# G11-KeyDispPrint.net
KiCad netlist of a schematic drawn in Altium Designer
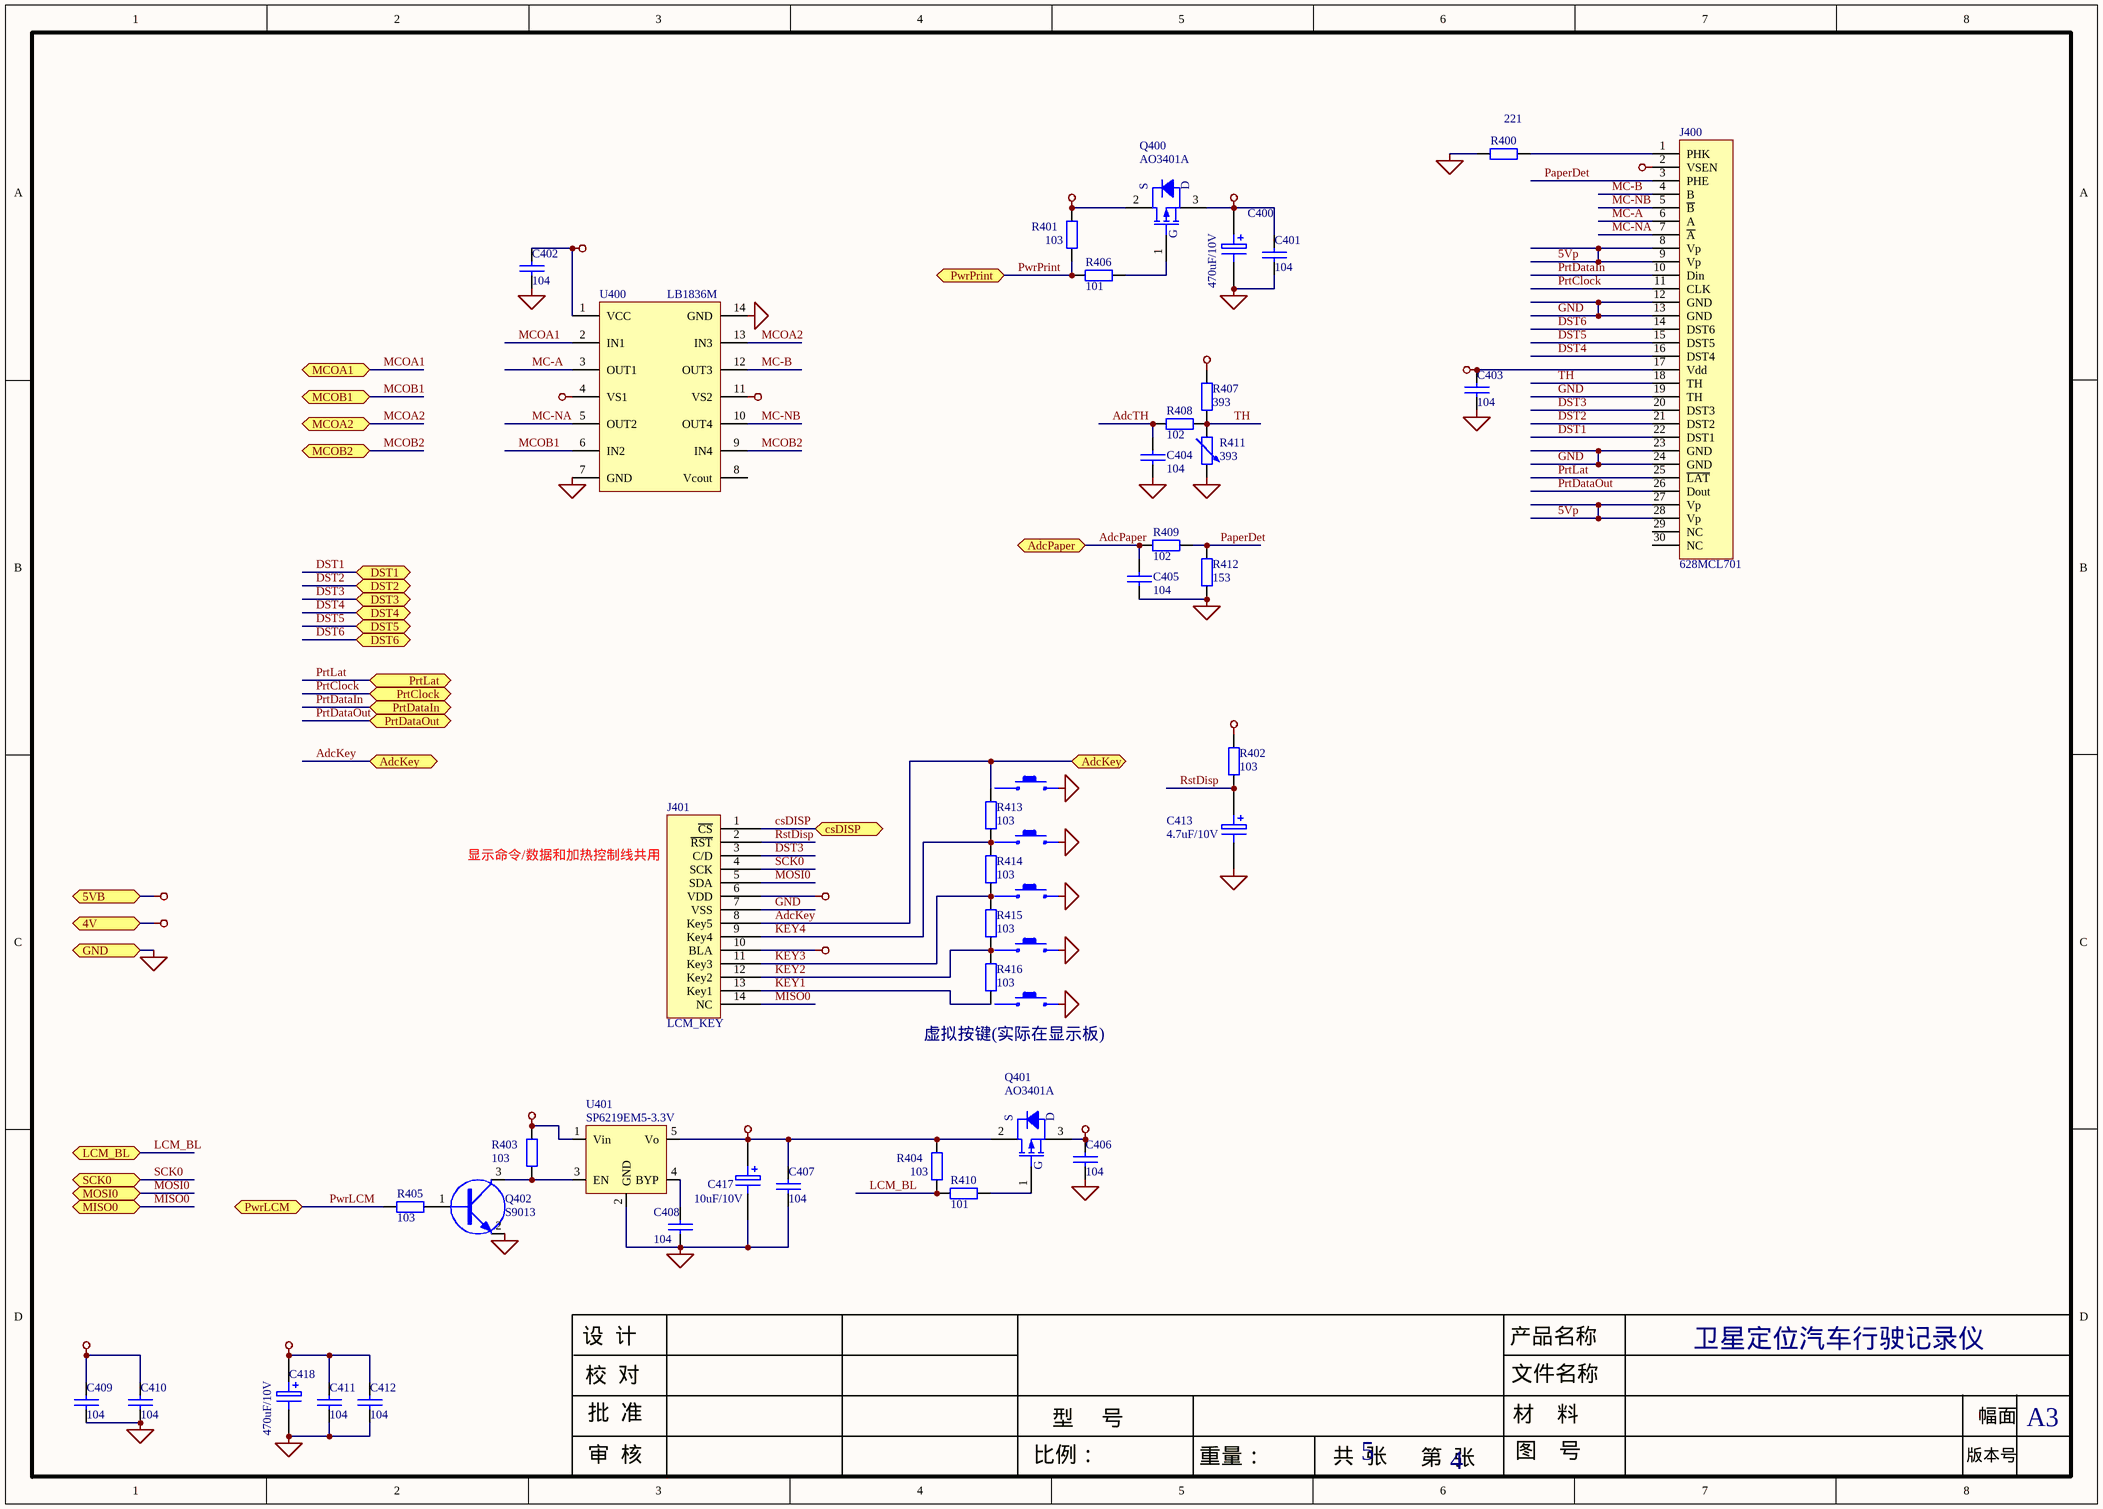
[diagram p0: G11-KeyDispPrint.SCHDOC]

(export (version "E")
  (design (tool "Eeschema 10.0.6"))
  (components
    (comp (ref "C400")
      (value "470uF/10V")
      (footprint "RB-3.5mm")
      (description "直插电解")
      (libsource (lib "*") (part "ELECTRO1"))
    )
    (comp (ref "C401")
      (value "104")
      (footprint "C0603")
      (description "Capacitor")
      (libsource (lib "*") (part "CAP"))
    )
    (comp (ref "C402")
      (value "104")
      (footprint "C0603")
      (description "Capacitor")
      (libsource (lib "*") (part "CAP"))
    )
    (comp (ref "C403")
      (value "104")
      (footprint "C0603")
      (description "Capacitor")
      (libsource (lib "*") (part "CAP"))
    )
    (comp (ref "C404")
      (value "104")
      (footprint "C0603")
      (description "Capacitor")
      (libsource (lib "*") (part "CAP"))
    )
    (comp (ref "C405")
      (value "104")
      (footprint "C0603")
      (description "Capacitor")
      (libsource (lib "*") (part "CAP"))
    )
    (comp (ref "C406")
      (value "104")
      (footprint "C0603")
      (description "Capacitor")
      (libsource (lib "*") (part "CAP"))
    )
    (comp (ref "C407")
      (value "104")
      (footprint "C0603")
      (description "Capacitor")
      (libsource (lib "*") (part "CAP"))
    )
    (comp (ref "C408")
      (value "104")
      (footprint "C0603")
      (description "Capacitor")
      (libsource (lib "*") (part "CAP"))
    )
    (comp (ref "C409")
      (value "104")
      (footprint "C0603")
      (description "Capacitor")
      (libsource (lib "*") (part "CAP"))
    )
    (comp (ref "C410")
      (value "104")
      (footprint "C0603")
      (description "Capacitor")
      (libsource (lib "*") (part "CAP"))
    )
    (comp (ref "C411")
      (value "104")
      (footprint "C0603")
      (description "Capacitor")
      (libsource (lib "*") (part "CAP"))
    )
    (comp (ref "C412")
      (value "104")
      (footprint "C0603")
      (description "Capacitor")
      (libsource (lib "*") (part "CAP"))
    )
    (comp (ref "C413")
      (value "4.7uF/10V")
      (footprint "A(3216)")
      (description "贴片钽电容")
      (libsource (lib "*") (part "ELECTRO1"))
    )
    (comp (ref "C417")
      (value "10uF/10V")
      (footprint "A(3216)")
      (description "贴片钽电容")
      (libsource (lib "*") (part "ELECTRO1"))
    )
    (comp (ref "C418")
      (value "470uF/10V")
      (footprint "RB-3.5mm")
      (description "直插电解")
      (libsource (lib "*") (part "ELECTRO1"))
    )
    (comp (ref "J400")
      (value "628MCL701")
      (footprint "FPC-30H")
      (description "贴片竖焊打印机接口")
      (libsource (lib "GY-G10A_1") (part "628MCL701"))
    )
    (comp (ref "J401") (value "LCM_KEY") (footprint "FPC-14-1.0") (libsource (lib "GY-G11") (part "LCM_KEY")))
    (comp (ref "Q400")
      (value "AO3401A")
      (footprint "SOT-233PM")
      (description "贴片P沟MOS管")
      (libsource (lib "GY-G11") (part "MOSFET-P"))
    )
    (comp (ref "Q401")
      (value "AO3401A")
      (footprint "SOT-233PM")
      (description "贴片P沟MOS管")
      (libsource (lib "GY-G11") (part "MOSFET-P"))
    )
    (comp (ref "Q402") (value "S9013") (footprint "SOT-233") (libsource (lib "SimpleGPS") (part "9013")))
    (comp (ref "R400")
      (value "221")
      (footprint "R0603")
      (description "贴片电阻")
      (fields
        (field (name "MANUFACTURER") "Generic Components")
        (field (name "PUBLISHER") "Altium Hobart Technology Centre")
      )
      (libsource (lib "") (part "Res2_4"))
    )
    (comp (ref "R401")
      (value "103")
      (footprint "R0603")
      (description "贴片电阻")
      (fields
        (field (name "MANUFACTURER") "Generic Components")
        (field (name "PUBLISHER") "Altium Hobart Technology Centre")
      )
      (libsource (lib "LPC213_General") (part "Res2"))
    )
    (comp (ref "R402")
      (value "103")
      (footprint "R0603")
      (description "贴片电阻")
      (fields
        (field (name "MANUFACTURER") "Generic Components")
        (field (name "PUBLISHER") "Altium Hobart Technology Centre")
      )
      (libsource (lib "LPC213_General") (part "Res2"))
    )
    (comp (ref "R403")
      (value "103")
      (footprint "R0603")
      (description "贴片电阻")
      (fields
        (field (name "MANUFACTURER") "Generic Components")
        (field (name "PUBLISHER") "Altium Hobart Technology Centre")
      )
      (libsource (lib "") (part "Res2_3"))
    )
    (comp (ref "R404")
      (value "103")
      (footprint "R0603")
      (description "贴片电阻")
      (fields
        (field (name "MANUFACTURER") "Generic Components")
        (field (name "PUBLISHER") "Altium Hobart Technology Centre")
      )
      (libsource (lib "LPC213_General") (part "Res2"))
    )
    (comp (ref "R405")
      (value "103")
      (footprint "R0603")
      (description "贴片电阻")
      (fields
        (field (name "MANUFACTURER") "Generic Components")
        (field (name "PUBLISHER") "Altium Hobart Technology Centre")
      )
      (libsource (lib "") (part "Res2_2"))
    )
    (comp (ref "R406")
      (value "101")
      (footprint "R0603")
      (description "贴片电阻")
      (fields
        (field (name "MANUFACTURER") "Generic Components")
        (field (name "PUBLISHER") "Altium Hobart Technology Centre")
      )
      (libsource (lib "GY-VT08M") (part "Res2"))
    )
    (comp (ref "R407")
      (value "393")
      (footprint "R0603")
      (description "贴片电阻")
      (fields
        (field (name "MANUFACTURER") "Generic Components")
        (field (name "PUBLISHER") "Altium Hobart Technology Centre")
      )
      (libsource (lib "") (part "Res2_2"))
    )
    (comp (ref "R408")
      (value "102")
      (footprint "R0603")
      (description "贴片电阻")
      (fields
        (field (name "MANUFACTURER") "Generic Components")
        (field (name "PUBLISHER") "Altium Hobart Technology Centre")
      )
      (libsource (lib "") (part "Res2_1"))
    )
    (comp (ref "R409")
      (value "102")
      (footprint "R0603")
      (description "贴片电阻")
      (fields
        (field (name "MANUFACTURER") "Generic Components")
        (field (name "PUBLISHER") "Altium Hobart Technology Centre")
      )
      (libsource (lib "") (part "Res2_1"))
    )
    (comp (ref "R410")
      (value "101")
      (footprint "R0603")
      (description "贴片电阻")
      (fields
        (field (name "MANUFACTURER") "Generic Components")
        (field (name "PUBLISHER") "Altium Hobart Technology Centre")
      )
      (libsource (lib "GY-VT08M") (part "Res2"))
    )
    (comp (ref "R411")
      (value "393")
      (footprint "0603")
      (description "贴片热敏电阻")
      (fields (field (name "Comment") "Res Adj2") (field (name "PUBLISHER") "Altium Limited"))
      (libsource (lib "Miscellaneous Devices") (part "Res Adj2"))
    )
    (comp (ref "R412")
      (value "153")
      (footprint "R0603")
      (description "贴片电阻")
      (fields
        (field (name "MANUFACTURER") "Generic Components")
        (field (name "PUBLISHER") "Altium Hobart Technology Centre")
      )
      (libsource (lib "") (part "Res2_2"))
    )
    (comp (ref "R413")
      (value "103")
      (footprint "R0603")
      (description "贴片电阻")
      (fields
        (field (name "MANUFACTURER") "Generic Components")
        (field (name "PUBLISHER") "Altium Hobart Technology Centre")
      )
      (libsource (lib "LPC213_General") (part "Res2"))
    )
    (comp (ref "R414")
      (value "103")
      (footprint "R0603")
      (description "贴片电阻")
      (fields
        (field (name "MANUFACTURER") "Generic Components")
        (field (name "PUBLISHER") "Altium Hobart Technology Centre")
      )
      (libsource (lib "LPC213_General") (part "Res2"))
    )
    (comp (ref "R415")
      (value "103")
      (footprint "R0603")
      (description "贴片电阻")
      (fields
        (field (name "MANUFACTURER") "Generic Components")
        (field (name "PUBLISHER") "Altium Hobart Technology Centre")
      )
      (libsource (lib "LPC213_General") (part "Res2"))
    )
    (comp (ref "R416")
      (value "103")
      (footprint "R0603")
      (description "贴片电阻")
      (fields
        (field (name "MANUFACTURER") "Generic Components")
        (field (name "PUBLISHER") "Altium Hobart Technology Centre")
      )
      (libsource (lib "LPC213_General") (part "Res2"))
    )
    (comp (ref "U400")
      (value "LB1836M")
      (footprint "SO-G14-1.0mm")
      (description "贴片IC")
      (libsource (lib "GY-G10A_1") (part "LB1836M"))
    )
    (comp (ref "U401")
      (value "SP6219EM5-3.3V")
      (footprint "SOT-235")
      (description "贴片电源LDO")
      (libsource (lib "*") (part "SPX5205"))
    )
  )
  (nets
    (net (code "1") (name "/AdcKey") (class "Default")
      (node (ref "J401") (pin "8") (pinfunction "Key5_8") (pintype "passive"))
      (node (ref "R413") (pin "1") (pinfunction "1_1") (pintype "passive"))
    )
    (net (code "2") (name "/AdcPaper") (class "Default")
      (node (ref "C405") (pin "1") (pinfunction "1_1") (pintype "passive"))
      (node (ref "R409") (pin "1") (pinfunction "1_1") (pintype "passive"))
    )
    (net (code "3") (name "/AdcTH") (class "Default")
      (node (ref "C404") (pin "1") (pinfunction "1_1") (pintype "passive"))
      (node (ref "R408") (pin "1") (pinfunction "1_1") (pintype "passive"))
    )
    (net (code "4") (name "/DST1") (class "Default")
      (node (ref "J400") (pin "22") (pinfunction "DST1_22") (pintype "passive"))
    )
    (net (code "5") (name "/DST2") (class "Default")
      (node (ref "J400") (pin "21") (pinfunction "DST2_21") (pintype "passive"))
    )
    (net (code "6") (name "/DST3") (class "Default")
      (node (ref "J400") (pin "20") (pinfunction "DST3_20") (pintype "passive"))
      (node (ref "J401") (pin "3") (pinfunction "C/D_3") (pintype "passive"))
    )
    (net (code "7") (name "/DST4") (class "Default")
      (node (ref "J400") (pin "16") (pinfunction "DST4_16") (pintype "passive"))
    )
    (net (code "8") (name "/DST5") (class "Default")
      (node (ref "J400") (pin "15") (pinfunction "DST5_15") (pintype "passive"))
    )
    (net (code "9") (name "/DST6") (class "Default")
      (node (ref "J400") (pin "14") (pinfunction "DST6_14") (pintype "passive"))
    )
    (net (code "10") (name "/KEY1") (class "Default")
      (node (ref "J401") (pin "13") (pinfunction "Key1_13") (pintype "passive"))
      (node (ref "R416") (pin "2") (pinfunction "2_2") (pintype "passive"))
    )
    (net (code "11") (name "/KEY2") (class "Default")
      (node (ref "J401") (pin "12") (pinfunction "Key2_12") (pintype "passive"))
      (node (ref "R415") (pin "2") (pinfunction "2_2") (pintype "passive"))
      (node (ref "R416") (pin "1") (pinfunction "1_1") (pintype "passive"))
    )
    (net (code "12") (name "/KEY3") (class "Default")
      (node (ref "J401") (pin "11") (pinfunction "Key3_11") (pintype "passive"))
      (node (ref "R414") (pin "2") (pinfunction "2_2") (pintype "passive"))
      (node (ref "R415") (pin "1") (pinfunction "1_1") (pintype "passive"))
    )
    (net (code "13") (name "/KEY4") (class "Default")
      (node (ref "J401") (pin "9") (pinfunction "Key4_9") (pintype "passive"))
      (node (ref "R413") (pin "2") (pinfunction "2_2") (pintype "passive"))
      (node (ref "R414") (pin "1") (pinfunction "1_1") (pintype "passive"))
    )
    (net (code "14") (name "/LCM_BL") (class "Default")
      (node (ref "R404") (pin "2") (pinfunction "2_2") (pintype "passive"))
      (node (ref "R410") (pin "2") (pinfunction "2_2") (pintype "passive"))
    )
    (net (code "15") (name "/MC-A") (class "Default")
      (node (ref "J400") (pin "6") (pinfunction "A_6") (pintype "passive"))
      (node (ref "U400") (pin "3") (pinfunction "OUT1_3") (pintype "passive"))
    )
    (net (code "16") (name "/MC-B") (class "Default")
      (node (ref "J400") (pin "4") (pinfunction "B_4") (pintype "passive"))
      (node (ref "U400") (pin "12") (pinfunction "OUT3_12") (pintype "passive"))
    )
    (net (code "17") (name "/MC-NA") (class "Default")
      (node (ref "J400") (pin "7") (pinfunction "~{A}_7") (pintype "passive"))
      (node (ref "U400") (pin "5") (pinfunction "OUT2_5") (pintype "passive"))
    )
    (net (code "18") (name "/MC-NB") (class "Default")
      (node (ref "J400") (pin "5") (pinfunction "~{B}_5") (pintype "passive"))
      (node (ref "U400") (pin "10") (pinfunction "OUT4_10") (pintype "passive"))
    )
    (net (code "19") (name "/MCOA1") (class "Default")
      (node (ref "U400") (pin "2") (pinfunction "IN1_2") (pintype "passive"))
    )
    (net (code "20") (name "/MCOA2") (class "Default")
      (node (ref "U400") (pin "13") (pinfunction "IN3_13") (pintype "passive"))
    )
    (net (code "21") (name "/MCOB1") (class "Default")
      (node (ref "U400") (pin "6") (pinfunction "IN2_6") (pintype "passive"))
    )
    (net (code "22") (name "/MCOB2") (class "Default")
      (node (ref "U400") (pin "9") (pinfunction "IN4_9") (pintype "passive"))
    )
    (net (code "23") (name "/MISO0") (class "Default")
      (node (ref "J401") (pin "14") (pinfunction "NC_14") (pintype "passive"))
    )
    (net (code "24") (name "/MOSI0") (class "Default")
      (node (ref "J401") (pin "5") (pinfunction "SDA_5") (pintype "passive"))
    )
    (net (code "25") (name "/PaperDet") (class "Default")
      (node (ref "J400") (pin "3") (pinfunction "PHE_3") (pintype "passive"))
      (node (ref "R409") (pin "2") (pinfunction "2_2") (pintype "passive"))
      (node (ref "R412") (pin "1") (pinfunction "1_1") (pintype "passive"))
    )
    (net (code "26") (name "/PrtClock") (class "Default")
      (node (ref "J400") (pin "11") (pinfunction "CLK_11") (pintype "passive"))
    )
    (net (code "27") (name "/PrtDataIn") (class "Default")
      (node (ref "J400") (pin "10") (pinfunction "Din_10") (pintype "passive"))
    )
    (net (code "28") (name "/PrtDataOut") (class "Default")
      (node (ref "J400") (pin "26") (pinfunction "Dout_26") (pintype "passive"))
    )
    (net (code "29") (name "/PrtLat") (class "Default")
      (node (ref "J400") (pin "25") (pinfunction "~{LAT}_25") (pintype "passive"))
    )
    (net (code "30") (name "/PwrLCM") (class "Default")
      (node (ref "R405") (pin "2") (pinfunction "2_2") (pintype "passive"))
    )
    (net (code "31") (name "/PwrPrint") (class "Default")
      (node (ref "R401") (pin "2") (pinfunction "2_2") (pintype "passive"))
      (node (ref "R406") (pin "2") (pinfunction "2_2") (pintype "passive"))
    )
    (net (code "32") (name "/RstDisp") (class "Default")
      (node (ref "C413") (pin "1") (pinfunction "1_1") (pintype "passive"))
      (node (ref "J401") (pin "2") (pinfunction "~{RST}_2") (pintype "passive"))
      (node (ref "R402") (pin "2") (pinfunction "2_2") (pintype "passive"))
    )
    (net (code "33") (name "/SCK0") (class "Default")
      (node (ref "J401") (pin "4") (pinfunction "SCK_4") (pintype "passive"))
    )
    (net (code "34") (name "/TH") (class "Default")
      (node (ref "J400") (pin "18") (pinfunction "TH_18") (pintype "passive"))
      (node (ref "R407") (pin "2") (pinfunction "2_2") (pintype "passive"))
      (node (ref "R408") (pin "2") (pinfunction "2_2") (pintype "passive"))
      (node (ref "R411") (pin "1") (pinfunction "1_1") (pintype "passive"))
    )
    (net (code "35") (name "/csDISP") (class "Default")
      (node (ref "J401") (pin "1") (pinfunction "~{CS}_1") (pintype "passive"))
    )
    (net (code "36") (name "3V3Lcm") (class "Default")
      (node (ref "C407") (pin "2") (pinfunction "2_2") (pintype "passive"))
      (node (ref "C417") (pin "1") (pinfunction "1_1") (pintype "passive"))
      (node (ref "J401") (pin "6") (pinfunction "VDD_6") (pintype "passive"))
      (node (ref "Q401") (pin "2") (pinfunction "D_2") (pintype "passive"))
      (node (ref "R402") (pin "1") (pinfunction "1_1") (pintype "passive"))
      (node (ref "R404") (pin "1") (pinfunction "1_1") (pintype "passive"))
      (node (ref "U401") (pin "5") (pinfunction "Vo_5") (pintype "passive"))
    )
    (net (code "37") (name "3V_BL") (class "Default")
      (node (ref "C406") (pin "2") (pinfunction "2_2") (pintype "passive"))
      (node (ref "J401") (pin "10") (pinfunction "BLA_10") (pintype "passive"))
      (node (ref "Q401") (pin "3") (pinfunction "S_3") (pintype "passive"))
    )
    (net (code "38") (name "4V") (class "Default")
      (node (ref "R403") (pin "2") (pinfunction "2_2") (pintype "passive"))
      (node (ref "U401") (pin "1") (pinfunction "Vin_1") (pintype "passive"))
    )
    (net (code "39") (name "5VB") (class "Default")
      (node (ref "C402") (pin "2") (pinfunction "2_2") (pintype "passive"))
      (node (ref "C409") (pin "2") (pinfunction "2_2") (pintype "passive"))
      (node (ref "C410") (pin "2") (pinfunction "2_2") (pintype "passive"))
      (node (ref "C411") (pin "2") (pinfunction "2_2") (pintype "passive"))
      (node (ref "C412") (pin "2") (pinfunction "2_2") (pintype "passive"))
      (node (ref "C418") (pin "1") (pinfunction "1_1") (pintype "passive"))
      (node (ref "Q400") (pin "2") (pinfunction "D_2") (pintype "passive"))
      (node (ref "R401") (pin "1") (pinfunction "1_1") (pintype "passive"))
      (node (ref "R407") (pin "1") (pinfunction "1_1") (pintype "passive"))
      (node (ref "U400") (pin "1") (pinfunction "VCC_1") (pintype "passive"))
      (node (ref "U400") (pin "11") (pinfunction "VS2_11") (pintype "passive"))
      (node (ref "U400") (pin "4") (pinfunction "VS1_4") (pintype "passive"))
    )
    (net (code "40") (name "5Vp") (class "Default")
      (node (ref "C400") (pin "1") (pinfunction "1_1") (pintype "passive"))
      (node (ref "C401") (pin "2") (pinfunction "2_2") (pintype "passive"))
      (node (ref "C403") (pin "2") (pinfunction "2_2") (pintype "passive"))
      (node (ref "J400") (pin "17") (pinfunction "Vdd_17") (pintype "passive"))
      (node (ref "J400") (pin "2") (pinfunction "VSEN_2") (pintype "passive"))
      (node (ref "J400") (pin "27") (pinfunction "Vp_27") (pintype "passive"))
      (node (ref "J400") (pin "28") (pinfunction "Vp_28") (pintype "passive"))
      (node (ref "J400") (pin "8") (pinfunction "Vp_8") (pintype "passive"))
      (node (ref "J400") (pin "9") (pinfunction "Vp_9") (pintype "passive"))
      (node (ref "Q400") (pin "3") (pinfunction "S_3") (pintype "passive"))
    )
    (net (code "41") (name "GND") (class "Default")
      (node (ref "C400") (pin "2") (pinfunction "2_2") (pintype "passive"))
      (node (ref "C401") (pin "1") (pinfunction "1_1") (pintype "passive"))
      (node (ref "C402") (pin "1") (pinfunction "1_1") (pintype "passive"))
      (node (ref "C403") (pin "1") (pinfunction "1_1") (pintype "passive"))
      (node (ref "C404") (pin "2") (pinfunction "2_2") (pintype "passive"))
      (node (ref "C405") (pin "2") (pinfunction "2_2") (pintype "passive"))
      (node (ref "C406") (pin "1") (pinfunction "1_1") (pintype "passive"))
      (node (ref "C407") (pin "1") (pinfunction "1_1") (pintype "passive"))
      (node (ref "C408") (pin "1") (pinfunction "1_1") (pintype "passive"))
      (node (ref "C409") (pin "1") (pinfunction "1_1") (pintype "passive"))
      (node (ref "C410") (pin "1") (pinfunction "1_1") (pintype "passive"))
      (node (ref "C411") (pin "1") (pinfunction "1_1") (pintype "passive"))
      (node (ref "C412") (pin "1") (pinfunction "1_1") (pintype "passive"))
      (node (ref "C413") (pin "2") (pinfunction "2_2") (pintype "passive"))
      (node (ref "C417") (pin "2") (pinfunction "2_2") (pintype "passive"))
      (node (ref "C418") (pin "2") (pinfunction "2_2") (pintype "passive"))
      (node (ref "J400") (pin "12") (pinfunction "GND_12") (pintype "passive"))
      (node (ref "J400") (pin "13") (pinfunction "GND_13") (pintype "passive"))
      (node (ref "J400") (pin "19") (pinfunction "TH_19") (pintype "passive"))
      (node (ref "J400") (pin "23") (pinfunction "GND_23") (pintype "passive"))
      (node (ref "J400") (pin "24") (pinfunction "GND_24") (pintype "passive"))
      (node (ref "J401") (pin "7") (pinfunction "VSS_7") (pintype "passive"))
      (node (ref "Q402") (pin "2") (pinfunction "E_2") (pintype "passive"))
      (node (ref "R400") (pin "1") (pinfunction "1_1") (pintype "passive"))
      (node (ref "R411") (pin "2") (pinfunction "2_2") (pintype "passive"))
      (node (ref "R412") (pin "2") (pinfunction "2_2") (pintype "passive"))
      (node (ref "U400") (pin "14") (pinfunction "GND_14") (pintype "passive"))
      (node (ref "U400") (pin "7") (pinfunction "GND_7") (pintype "passive"))
      (node (ref "U401") (pin "2") (pinfunction "GND_2") (pintype "passive"))
    )
    (net (code "42") (name "Net-(J400-PHK)") (class "Default")
      (node (ref "J400") (pin "1") (pinfunction "PHK_1") (pintype "passive"))
      (node (ref "R400") (pin "2") (pinfunction "2_2") (pintype "passive"))
    )
    (net (code "43") (name "Net-(Q400-G)") (class "Default")
      (node (ref "Q400") (pin "1") (pinfunction "G_1") (pintype "passive"))
      (node (ref "R406") (pin "1") (pinfunction "1_1") (pintype "passive"))
    )
    (net (code "44") (name "Net-(Q401-G)") (class "Default")
      (node (ref "Q401") (pin "1") (pinfunction "G_1") (pintype "passive"))
      (node (ref "R410") (pin "1") (pinfunction "1_1") (pintype "passive"))
    )
    (net (code "45") (name "Net-(Q402-B)") (class "Default")
      (node (ref "Q402") (pin "1") (pinfunction "B_1") (pintype "passive"))
      (node (ref "R405") (pin "1") (pinfunction "1_1") (pintype "passive"))
    )
    (net (code "46") (name "Net-(Q402-C)") (class "Default")
      (node (ref "Q402") (pin "3") (pinfunction "C_3") (pintype "passive"))
      (node (ref "R403") (pin "1") (pinfunction "1_1") (pintype "passive"))
      (node (ref "U401") (pin "3") (pinfunction "EN_3") (pintype "passive"))
    )
    (net (code "47") (name "Net-(U401-BYP)") (class "Default")
      (node (ref "C408") (pin "2") (pinfunction "2_2") (pintype "passive"))
      (node (ref "U401") (pin "4") (pinfunction "BYP_4") (pintype "passive"))
    )
    (net (code "48") (name "unconnected-(J400-NC-Pad29)") (class "Default")
      (node (ref "J400") (pin "29") (pinfunction "NC_29") (pintype "passive"))
    )
    (net (code "49") (name "unconnected-(J400-NC-Pad30)") (class "Default")
      (node (ref "J400") (pin "30") (pinfunction "NC_30") (pintype "passive"))
    )
    (net (code "50") (name "unconnected-(U400-Vcout-Pad8)") (class "Default")
      (node (ref "U400") (pin "8") (pinfunction "Vcout_8") (pintype "passive"))
    )
  )
)
